# 2_bootleg-4-matrix.net
KiCad netlist of a schematic drawn in Altium Designer
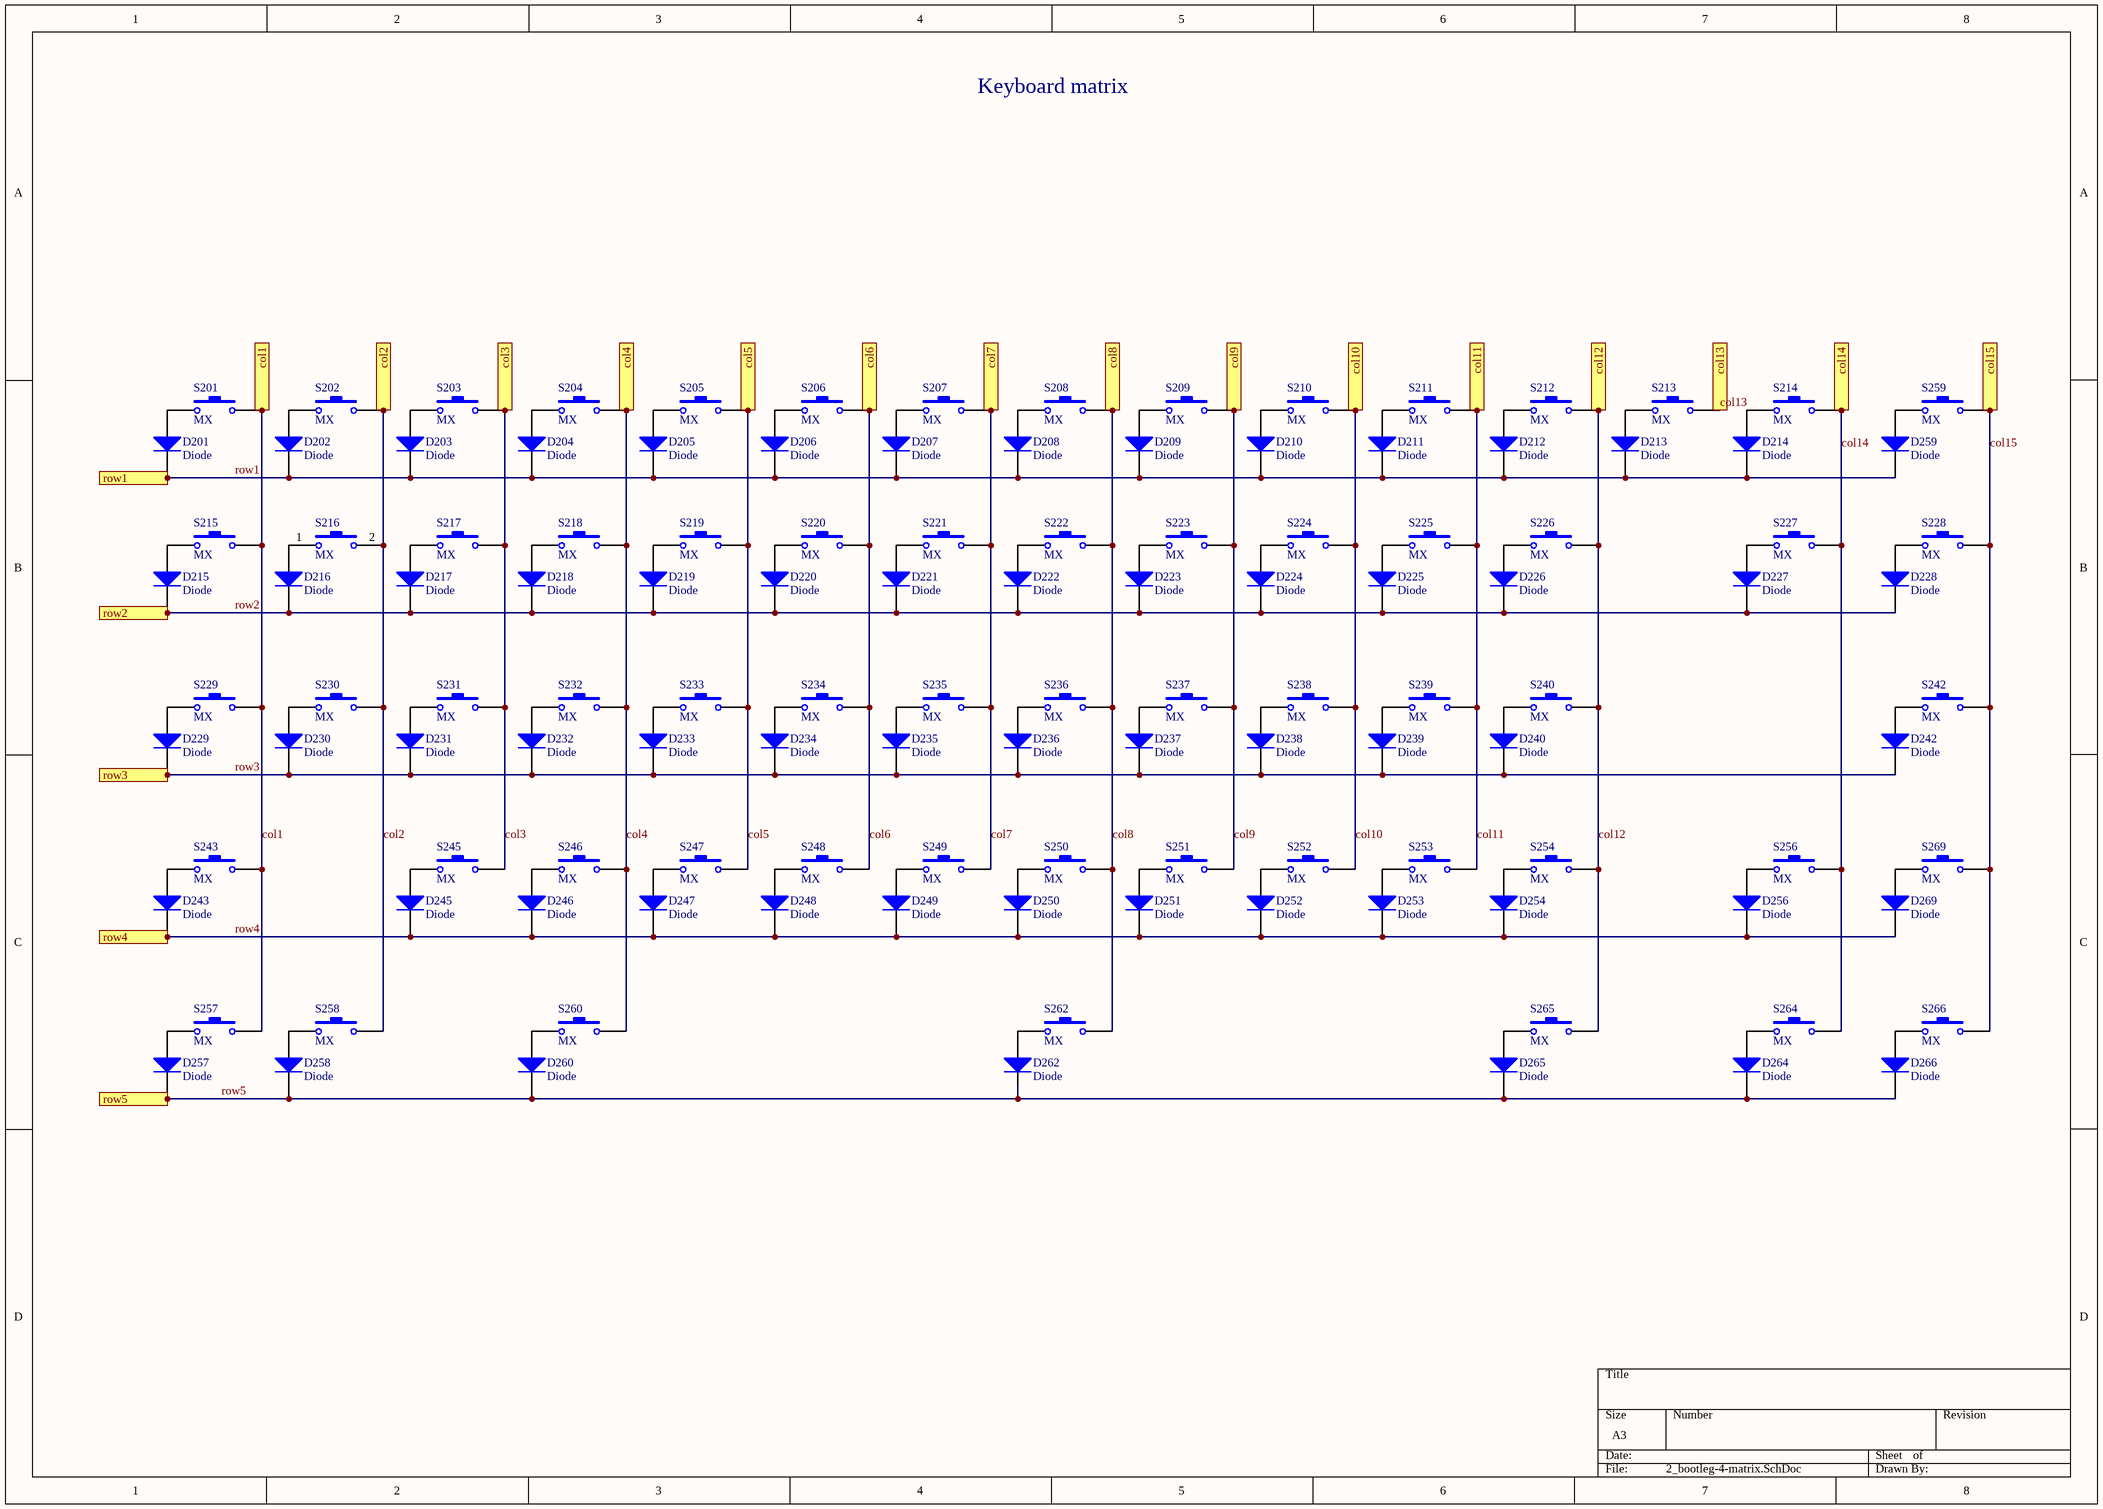
[diagram p0: 2_bootleg-4-matrix.SchDoc]

(export (version "E")
  (design (tool "Eeschema 10.0.6"))
  (components
    (comp (ref "D201")
      (value "Diode")
      (footprint "SOD-123")
      (description "Default Diode")
      (fields (field (name "MFG") "Bourns Inc.") (field (name "LCSC PART #") "C109002"))
      (libsource (lib "Miscellaneous Devices") (part "Diode"))
    )
    (comp (ref "D202")
      (value "Diode")
      (footprint "SOD-123")
      (description "Default Diode")
      (fields (field (name "MFG") "Bourns Inc.") (field (name "LCSC PART #") "C109002"))
      (libsource (lib "Miscellaneous Devices") (part "Diode"))
    )
    (comp (ref "D203")
      (value "Diode")
      (footprint "SOD-123")
      (description "Default Diode")
      (fields (field (name "MFG") "Bourns Inc.") (field (name "LCSC PART #") "C109002"))
      (libsource (lib "Miscellaneous Devices") (part "Diode"))
    )
    (comp (ref "D204")
      (value "Diode")
      (footprint "SOD-123")
      (description "Default Diode")
      (fields (field (name "MFG") "Bourns Inc.") (field (name "LCSC PART #") "C109002"))
      (libsource (lib "Miscellaneous Devices") (part "Diode"))
    )
    (comp (ref "D205")
      (value "Diode")
      (footprint "SOD-123")
      (description "Default Diode")
      (fields (field (name "MFG") "Bourns Inc.") (field (name "LCSC PART #") "C109002"))
      (libsource (lib "Miscellaneous Devices") (part "Diode"))
    )
    (comp (ref "D206")
      (value "Diode")
      (footprint "SOD-123")
      (description "Default Diode")
      (fields (field (name "MFG") "Bourns Inc.") (field (name "LCSC PART #") "C109002"))
      (libsource (lib "Miscellaneous Devices") (part "Diode"))
    )
    (comp (ref "D207")
      (value "Diode")
      (footprint "SOD-123")
      (description "Default Diode")
      (fields (field (name "MFG") "Bourns Inc.") (field (name "LCSC PART #") "C109002"))
      (libsource (lib "Miscellaneous Devices") (part "Diode"))
    )
    (comp (ref "D208")
      (value "Diode")
      (footprint "SOD-123")
      (description "Default Diode")
      (fields (field (name "MFG") "Bourns Inc.") (field (name "LCSC PART #") "C109002"))
      (libsource (lib "Miscellaneous Devices") (part "Diode"))
    )
    (comp (ref "D209")
      (value "Diode")
      (footprint "SOD-123")
      (description "Default Diode")
      (fields (field (name "MFG") "Bourns Inc.") (field (name "LCSC PART #") "C109002"))
      (libsource (lib "Miscellaneous Devices") (part "Diode"))
    )
    (comp (ref "D210")
      (value "Diode")
      (footprint "SOD-123")
      (description "Default Diode")
      (fields (field (name "MFG") "Bourns Inc.") (field (name "LCSC PART #") "C109002"))
      (libsource (lib "Miscellaneous Devices") (part "Diode"))
    )
    (comp (ref "D211")
      (value "Diode")
      (footprint "SOD-123")
      (description "Default Diode")
      (fields (field (name "MFG") "Bourns Inc.") (field (name "LCSC PART #") "C109002"))
      (libsource (lib "Miscellaneous Devices") (part "Diode"))
    )
    (comp (ref "D212")
      (value "Diode")
      (footprint "SOD-123")
      (description "Default Diode")
      (fields (field (name "MFG") "Bourns Inc.") (field (name "LCSC PART #") "C109002"))
      (libsource (lib "Miscellaneous Devices") (part "Diode"))
    )
    (comp (ref "D213")
      (value "Diode")
      (footprint "SOD-123")
      (description "Default Diode")
      (fields (field (name "MFG") "Bourns Inc.") (field (name "LCSC PART #") "C109002"))
      (libsource (lib "Miscellaneous Devices") (part "Diode"))
    )
    (comp (ref "D214")
      (value "Diode")
      (footprint "SOD-123")
      (description "Default Diode")
      (fields (field (name "MFG") "Bourns Inc.") (field (name "LCSC PART #") "C109002"))
      (libsource (lib "Miscellaneous Devices") (part "Diode"))
    )
    (comp (ref "D215")
      (value "Diode")
      (footprint "SOD-123")
      (description "Default Diode")
      (fields (field (name "MFG") "Bourns Inc.") (field (name "LCSC PART #") "C109002"))
      (libsource (lib "Miscellaneous Devices") (part "Diode"))
    )
    (comp (ref "D216")
      (value "Diode")
      (footprint "SOD-123")
      (description "Default Diode")
      (fields (field (name "MFG") "Bourns Inc.") (field (name "LCSC PART #") "C109002"))
      (libsource (lib "Miscellaneous Devices") (part "Diode"))
    )
    (comp (ref "D217")
      (value "Diode")
      (footprint "SOD-123")
      (description "Default Diode")
      (fields (field (name "MFG") "Bourns Inc.") (field (name "LCSC PART #") "C109002"))
      (libsource (lib "Miscellaneous Devices") (part "Diode"))
    )
    (comp (ref "D218")
      (value "Diode")
      (footprint "SOD-123")
      (description "Default Diode")
      (fields (field (name "MFG") "Bourns Inc.") (field (name "LCSC PART #") "C109002"))
      (libsource (lib "Miscellaneous Devices") (part "Diode"))
    )
    (comp (ref "D219")
      (value "Diode")
      (footprint "SOD-123")
      (description "Default Diode")
      (fields (field (name "MFG") "Bourns Inc.") (field (name "LCSC PART #") "C109002"))
      (libsource (lib "Miscellaneous Devices") (part "Diode"))
    )
    (comp (ref "D220")
      (value "Diode")
      (footprint "SOD-123")
      (description "Default Diode")
      (fields (field (name "MFG") "Bourns Inc.") (field (name "LCSC PART #") "C109002"))
      (libsource (lib "Miscellaneous Devices") (part "Diode"))
    )
    (comp (ref "D221")
      (value "Diode")
      (footprint "SOD-123")
      (description "Default Diode")
      (fields (field (name "MFG") "Bourns Inc.") (field (name "LCSC PART #") "C109002"))
      (libsource (lib "Miscellaneous Devices") (part "Diode"))
    )
    (comp (ref "D222")
      (value "Diode")
      (footprint "SOD-123")
      (description "Default Diode")
      (fields (field (name "MFG") "Bourns Inc.") (field (name "LCSC PART #") "C109002"))
      (libsource (lib "Miscellaneous Devices") (part "Diode"))
    )
    (comp (ref "D223")
      (value "Diode")
      (footprint "SOD-123")
      (description "Default Diode")
      (fields (field (name "MFG") "Bourns Inc.") (field (name "LCSC PART #") "C109002"))
      (libsource (lib "Miscellaneous Devices") (part "Diode"))
    )
    (comp (ref "D224")
      (value "Diode")
      (footprint "SOD-123")
      (description "Default Diode")
      (fields (field (name "MFG") "Bourns Inc.") (field (name "LCSC PART #") "C109002"))
      (libsource (lib "Miscellaneous Devices") (part "Diode"))
    )
    (comp (ref "D225")
      (value "Diode")
      (footprint "SOD-123")
      (description "Default Diode")
      (fields (field (name "MFG") "Bourns Inc.") (field (name "LCSC PART #") "C109002"))
      (libsource (lib "Miscellaneous Devices") (part "Diode"))
    )
    (comp (ref "D226")
      (value "Diode")
      (footprint "SOD-123")
      (description "Default Diode")
      (fields (field (name "MFG") "Bourns Inc.") (field (name "LCSC PART #") "C109002"))
      (libsource (lib "Miscellaneous Devices") (part "Diode"))
    )
    (comp (ref "D227")
      (value "Diode")
      (footprint "SOD-123")
      (description "Default Diode")
      (fields (field (name "MFG") "Bourns Inc.") (field (name "LCSC PART #") "C109002"))
      (libsource (lib "Miscellaneous Devices") (part "Diode"))
    )
    (comp (ref "D228")
      (value "Diode")
      (footprint "SOD-123")
      (description "Default Diode")
      (fields (field (name "MFG") "Bourns Inc.") (field (name "LCSC PART #") "C109002"))
      (libsource (lib "Miscellaneous Devices") (part "Diode"))
    )
    (comp (ref "D229")
      (value "Diode")
      (footprint "SOD-123")
      (description "Default Diode")
      (fields (field (name "MFG") "Bourns Inc.") (field (name "LCSC PART #") "C109002"))
      (libsource (lib "Miscellaneous Devices") (part "Diode"))
    )
    (comp (ref "D230")
      (value "Diode")
      (footprint "SOD-123")
      (description "Default Diode")
      (fields (field (name "MFG") "Bourns Inc.") (field (name "LCSC PART #") "C109002"))
      (libsource (lib "Miscellaneous Devices") (part "Diode"))
    )
    (comp (ref "D231")
      (value "Diode")
      (footprint "SOD-123")
      (description "Default Diode")
      (fields (field (name "MFG") "Bourns Inc.") (field (name "LCSC PART #") "C109002"))
      (libsource (lib "Miscellaneous Devices") (part "Diode"))
    )
    (comp (ref "D232")
      (value "Diode")
      (footprint "SOD-123")
      (description "Default Diode")
      (fields (field (name "MFG") "Bourns Inc.") (field (name "LCSC PART #") "C109002"))
      (libsource (lib "Miscellaneous Devices") (part "Diode"))
    )
    (comp (ref "D233")
      (value "Diode")
      (footprint "SOD-123")
      (description "Default Diode")
      (fields (field (name "MFG") "Bourns Inc.") (field (name "LCSC PART #") "C109002"))
      (libsource (lib "Miscellaneous Devices") (part "Diode"))
    )
    (comp (ref "D234")
      (value "Diode")
      (footprint "SOD-123")
      (description "Default Diode")
      (fields (field (name "MFG") "Bourns Inc.") (field (name "LCSC PART #") "C109002"))
      (libsource (lib "Miscellaneous Devices") (part "Diode"))
    )
    (comp (ref "D235")
      (value "Diode")
      (footprint "SOD-123")
      (description "Default Diode")
      (fields (field (name "MFG") "Bourns Inc.") (field (name "LCSC PART #") "C109002"))
      (libsource (lib "Miscellaneous Devices") (part "Diode"))
    )
    (comp (ref "D236")
      (value "Diode")
      (footprint "SOD-123")
      (description "Default Diode")
      (fields (field (name "MFG") "Bourns Inc.") (field (name "LCSC PART #") "C109002"))
      (libsource (lib "Miscellaneous Devices") (part "Diode"))
    )
    (comp (ref "D237")
      (value "Diode")
      (footprint "SOD-123")
      (description "Default Diode")
      (fields (field (name "MFG") "Bourns Inc.") (field (name "LCSC PART #") "C109002"))
      (libsource (lib "Miscellaneous Devices") (part "Diode"))
    )
    (comp (ref "D238")
      (value "Diode")
      (footprint "SOD-123")
      (description "Default Diode")
      (fields (field (name "MFG") "Bourns Inc.") (field (name "LCSC PART #") "C109002"))
      (libsource (lib "Miscellaneous Devices") (part "Diode"))
    )
    (comp (ref "D239")
      (value "Diode")
      (footprint "SOD-123")
      (description "Default Diode")
      (fields (field (name "MFG") "Bourns Inc.") (field (name "LCSC PART #") "C109002"))
      (libsource (lib "Miscellaneous Devices") (part "Diode"))
    )
    (comp (ref "D240")
      (value "Diode")
      (footprint "SOD-123")
      (description "Default Diode")
      (fields (field (name "MFG") "Bourns Inc.") (field (name "LCSC PART #") "C109002"))
      (libsource (lib "Miscellaneous Devices") (part "Diode"))
    )
    (comp (ref "D242")
      (value "Diode")
      (footprint "SOD-123")
      (description "Default Diode")
      (fields (field (name "MFG") "Bourns Inc.") (field (name "LCSC PART #") "C109002"))
      (libsource (lib "Miscellaneous Devices") (part "Diode"))
    )
    (comp (ref "D243")
      (value "Diode")
      (footprint "SOD-123")
      (description "Default Diode")
      (fields (field (name "MFG") "Bourns Inc.") (field (name "LCSC PART #") "C109002"))
      (libsource (lib "Miscellaneous Devices") (part "Diode"))
    )
    (comp (ref "D245")
      (value "Diode")
      (footprint "SOD-123")
      (description "Default Diode")
      (fields (field (name "MFG") "Bourns Inc.") (field (name "LCSC PART #") "C109002"))
      (libsource (lib "Miscellaneous Devices") (part "Diode"))
    )
    (comp (ref "D246")
      (value "Diode")
      (footprint "SOD-123")
      (description "Default Diode")
      (fields (field (name "MFG") "Bourns Inc.") (field (name "LCSC PART #") "C109002"))
      (libsource (lib "Miscellaneous Devices") (part "Diode"))
    )
    (comp (ref "D247")
      (value "Diode")
      (footprint "SOD-123")
      (description "Default Diode")
      (fields (field (name "MFG") "Bourns Inc.") (field (name "LCSC PART #") "C109002"))
      (libsource (lib "Miscellaneous Devices") (part "Diode"))
    )
    (comp (ref "D248")
      (value "Diode")
      (footprint "SOD-123")
      (description "Default Diode")
      (fields (field (name "MFG") "Bourns Inc.") (field (name "LCSC PART #") "C109002"))
      (libsource (lib "Miscellaneous Devices") (part "Diode"))
    )
    (comp (ref "D249")
      (value "Diode")
      (footprint "SOD-123")
      (description "Default Diode")
      (fields (field (name "MFG") "Bourns Inc.") (field (name "LCSC PART #") "C109002"))
      (libsource (lib "Miscellaneous Devices") (part "Diode"))
    )
    (comp (ref "D250")
      (value "Diode")
      (footprint "SOD-123")
      (description "Default Diode")
      (fields (field (name "MFG") "Bourns Inc.") (field (name "LCSC PART #") "C109002"))
      (libsource (lib "Miscellaneous Devices") (part "Diode"))
    )
    (comp (ref "D251")
      (value "Diode")
      (footprint "SOD-123")
      (description "Default Diode")
      (fields (field (name "MFG") "Bourns Inc.") (field (name "LCSC PART #") "C109002"))
      (libsource (lib "Miscellaneous Devices") (part "Diode"))
    )
    (comp (ref "D252")
      (value "Diode")
      (footprint "SOD-123")
      (description "Default Diode")
      (fields (field (name "MFG") "Bourns Inc.") (field (name "LCSC PART #") "C109002"))
      (libsource (lib "Miscellaneous Devices") (part "Diode"))
    )
    (comp (ref "D253")
      (value "Diode")
      (footprint "SOD-123")
      (description "Default Diode")
      (fields (field (name "MFG") "Bourns Inc.") (field (name "LCSC PART #") "C109002"))
      (libsource (lib "Miscellaneous Devices") (part "Diode"))
    )
    (comp (ref "D254")
      (value "Diode")
      (footprint "SOD-123")
      (description "Default Diode")
      (fields (field (name "MFG") "Bourns Inc.") (field (name "LCSC PART #") "C109002"))
      (libsource (lib "Miscellaneous Devices") (part "Diode"))
    )
    (comp (ref "D256")
      (value "Diode")
      (footprint "SOD-123")
      (description "Default Diode")
      (fields (field (name "MFG") "Bourns Inc.") (field (name "LCSC PART #") "C109002"))
      (libsource (lib "Miscellaneous Devices") (part "Diode"))
    )
    (comp (ref "D257")
      (value "Diode")
      (footprint "SOD-123")
      (description "Default Diode")
      (fields (field (name "MFG") "Bourns Inc.") (field (name "LCSC PART #") "C109002"))
      (libsource (lib "Miscellaneous Devices") (part "Diode"))
    )
    (comp (ref "D258")
      (value "Diode")
      (footprint "SOD-123")
      (description "Default Diode")
      (fields (field (name "MFG") "Bourns Inc.") (field (name "LCSC PART #") "C109002"))
      (libsource (lib "Miscellaneous Devices") (part "Diode"))
    )
    (comp (ref "D259")
      (value "Diode")
      (footprint "SOD-123")
      (description "Default Diode")
      (fields (field (name "MFG") "Bourns Inc.") (field (name "LCSC PART #") "C109002"))
      (libsource (lib "Miscellaneous Devices") (part "Diode"))
    )
    (comp (ref "D260")
      (value "Diode")
      (footprint "SOD-123")
      (description "Default Diode")
      (fields (field (name "MFG") "Bourns Inc.") (field (name "LCSC PART #") "C109002"))
      (libsource (lib "Miscellaneous Devices") (part "Diode"))
    )
    (comp (ref "D262")
      (value "Diode")
      (footprint "SOD-123")
      (description "Default Diode")
      (fields (field (name "MFG") "Bourns Inc.") (field (name "LCSC PART #") "C109002"))
      (libsource (lib "Miscellaneous Devices") (part "Diode"))
    )
    (comp (ref "D264")
      (value "Diode")
      (footprint "SOD-123")
      (description "Default Diode")
      (fields (field (name "MFG") "Bourns Inc.") (field (name "LCSC PART #") "C109002"))
      (libsource (lib "Miscellaneous Devices") (part "Diode"))
    )
    (comp (ref "D265")
      (value "Diode")
      (footprint "SOD-123")
      (description "Default Diode")
      (fields (field (name "MFG") "Bourns Inc.") (field (name "LCSC PART #") "C109002"))
      (libsource (lib "Miscellaneous Devices") (part "Diode"))
    )
    (comp (ref "D266")
      (value "Diode")
      (footprint "SOD-123")
      (description "Default Diode")
      (fields (field (name "MFG") "Bourns Inc.") (field (name "LCSC PART #") "C109002"))
      (libsource (lib "Miscellaneous Devices") (part "Diode"))
    )
    (comp (ref "D269")
      (value "Diode")
      (footprint "SOD-123")
      (description "Default Diode")
      (fields (field (name "MFG") "Bourns Inc.") (field (name "LCSC PART #") "C109002"))
      (libsource (lib "Miscellaneous Devices") (part "Diode"))
    )
    (comp (ref "S201")
      (value "MX")
      (footprint "MX-switch - switched pol")
      (description "Switch")
      (libsource (lib "Miscellaneous Devices") (part "SW-PB"))
    )
    (comp (ref "S202")
      (value "MX")
      (footprint "MX-switch - switched pol")
      (description "Switch")
      (libsource (lib "Miscellaneous Devices") (part "SW-PB"))
    )
    (comp (ref "S203")
      (value "MX")
      (footprint "MX-switch - switched pol")
      (description "Switch")
      (libsource (lib "Miscellaneous Devices") (part "SW-PB"))
    )
    (comp (ref "S204")
      (value "MX")
      (footprint "MX-switch - switched pol")
      (description "Switch")
      (libsource (lib "Miscellaneous Devices") (part "SW-PB"))
    )
    (comp (ref "S205")
      (value "MX")
      (footprint "MX-switch - switched pol")
      (description "Switch")
      (libsource (lib "Miscellaneous Devices") (part "SW-PB"))
    )
    (comp (ref "S206")
      (value "MX")
      (footprint "MX-switch - switched pol")
      (description "Switch")
      (libsource (lib "Miscellaneous Devices") (part "SW-PB"))
    )
    (comp (ref "S207")
      (value "MX")
      (footprint "MX-switch - switched pol")
      (description "Switch")
      (libsource (lib "Miscellaneous Devices") (part "SW-PB"))
    )
    (comp (ref "S208")
      (value "MX")
      (footprint "MX-switch - switched pol")
      (description "Switch")
      (libsource (lib "Miscellaneous Devices") (part "SW-PB"))
    )
    (comp (ref "S209")
      (value "MX")
      (footprint "MX-switch - switched pol")
      (description "Switch")
      (libsource (lib "Miscellaneous Devices") (part "SW-PB"))
    )
    (comp (ref "S210")
      (value "MX")
      (footprint "MX-switch - switched pol")
      (description "Switch")
      (libsource (lib "Miscellaneous Devices") (part "SW-PB"))
    )
    (comp (ref "S211")
      (value "MX")
      (footprint "MX-switch - switched pol")
      (description "Switch")
      (libsource (lib "Miscellaneous Devices") (part "SW-PB"))
    )
    (comp (ref "S212")
      (value "MX")
      (footprint "MX-switch - switched pol")
      (description "Switch")
      (libsource (lib "Miscellaneous Devices") (part "SW-PB"))
    )
    (comp (ref "S213")
      (value "MX")
      (footprint "MX-switch - switched pol")
      (description "Switch")
      (libsource (lib "Miscellaneous Devices") (part "SW-PB"))
    )
    (comp (ref "S214")
      (value "MX")
      (footprint "MX-switch - switched pol")
      (description "Switch")
      (libsource (lib "Miscellaneous Devices") (part "SW-PB"))
    )
    (comp (ref "S215")
      (value "MX")
      (footprint "MX-switch - 1.5U")
      (description "TAB")
      (libsource (lib "Miscellaneous Devices") (part "SW-PB"))
    )
    (comp (ref "S216")
      (value "MX")
      (footprint "MX-switch - switched pol")
      (description "Switch")
      (libsource (lib "") (part "SW-PB_1"))
    )
    (comp (ref "S217")
      (value "MX")
      (footprint "MX-switch - switched pol")
      (description "Switch")
      (libsource (lib "Miscellaneous Devices") (part "SW-PB"))
    )
    (comp (ref "S218")
      (value "MX")
      (footprint "MX-switch - switched pol")
      (description "Switch")
      (libsource (lib "Miscellaneous Devices") (part "SW-PB"))
    )
    (comp (ref "S219")
      (value "MX")
      (footprint "MX-switch - switched pol")
      (description "Switch")
      (libsource (lib "Miscellaneous Devices") (part "SW-PB"))
    )
    (comp (ref "S220")
      (value "MX")
      (footprint "MX-switch - switched pol")
      (description "Switch")
      (libsource (lib "Miscellaneous Devices") (part "SW-PB"))
    )
    (comp (ref "S221")
      (value "MX")
      (footprint "MX-switch - switched pol")
      (description "Switch")
      (libsource (lib "Miscellaneous Devices") (part "SW-PB"))
    )
    (comp (ref "S222")
      (value "MX")
      (footprint "MX-switch - switched pol")
      (description "Switch")
      (libsource (lib "Miscellaneous Devices") (part "SW-PB"))
    )
    (comp (ref "S223")
      (value "MX")
      (footprint "MX-switch - switched pol")
      (description "Switch")
      (libsource (lib "Miscellaneous Devices") (part "SW-PB"))
    )
    (comp (ref "S224")
      (value "MX")
      (footprint "MX-switch - switched pol")
      (description "Switch")
      (libsource (lib "Miscellaneous Devices") (part "SW-PB"))
    )
    (comp (ref "S225")
      (value "MX")
      (footprint "MX-switch - switched pol")
      (description "Switch")
      (libsource (lib "Miscellaneous Devices") (part "SW-PB"))
    )
    (comp (ref "S226")
      (value "MX")
      (footprint "MX-switch")
      (description "Switch")
      (libsource (lib "Miscellaneous Devices") (part "SW-PB"))
    )
    (comp (ref "S227")
      (value "MX")
      (footprint "MX-switch - switched pol")
      (description "Switch")
      (libsource (lib "Miscellaneous Devices") (part "SW-PB"))
    )
    (comp (ref "S228")
      (value "MX")
      (footprint "MX-switch - 1.5U")
      (description "Switch")
      (libsource (lib "Miscellaneous Devices") (part "SW-PB"))
    )
    (comp (ref "S229")
      (value "MX")
      (footprint "MX-switch - CAPS")
      (description "Switch")
      (libsource (lib "Miscellaneous Devices") (part "SW-PB"))
    )
    (comp (ref "S230")
      (value "MX")
      (footprint "MX-switch - switched pol")
      (description "Switch")
      (libsource (lib "Miscellaneous Devices") (part "SW-PB"))
    )
    (comp (ref "S231")
      (value "MX")
      (footprint "MX-switch - switched pol")
      (description "Switch")
      (libsource (lib "Miscellaneous Devices") (part "SW-PB"))
    )
    (comp (ref "S232")
      (value "MX")
      (footprint "MX-switch - switched pol")
      (description "Switch")
      (libsource (lib "Miscellaneous Devices") (part "SW-PB"))
    )
    (comp (ref "S233")
      (value "MX")
      (footprint "MX-switch - switched pol")
      (description "Switch")
      (libsource (lib "Miscellaneous Devices") (part "SW-PB"))
    )
    (comp (ref "S234")
      (value "MX")
      (footprint "MX-switch - switched pol")
      (description "Switch")
      (libsource (lib "Miscellaneous Devices") (part "SW-PB"))
    )
    (comp (ref "S235")
      (value "MX")
      (footprint "MX-switch - switched pol")
      (description "Switch")
      (libsource (lib "Miscellaneous Devices") (part "SW-PB"))
    )
    (comp (ref "S236")
      (value "MX")
      (footprint "MX-switch - switched pol")
      (description "Switch")
      (libsource (lib "Miscellaneous Devices") (part "SW-PB"))
    )
    (comp (ref "S237")
      (value "MX")
      (footprint "MX-switch - switched pol")
      (description "Switch")
      (libsource (lib "Miscellaneous Devices") (part "SW-PB"))
    )
    (comp (ref "S238")
      (value "MX")
      (footprint "MX-switch - switched pol")
      (description "Switch")
      (libsource (lib "Miscellaneous Devices") (part "SW-PB"))
    )
    (comp (ref "S239")
      (value "MX")
      (footprint "MX-switch")
      (description "Switch")
      (libsource (lib "Miscellaneous Devices") (part "SW-PB"))
    )
    (comp (ref "S240")
      (value "MX")
      (footprint "MX-switch - switched pol")
      (description "Switch")
      (libsource (lib "Miscellaneous Devices") (part "SW-PB"))
    )
    (comp (ref "S242")
      (value "MX")
      (footprint "MX-switch - Enter_ANSI")
      (description "Switch")
      (libsource (lib "Miscellaneous Devices") (part "SW-PB"))
    )
    (comp (ref "S243")
      (value "MX")
      (footprint "MX-switch - 2.25U")
      (description "Switch")
      (libsource (lib "Miscellaneous Devices") (part "SW-PB"))
    )
    (comp (ref "S245")
      (value "MX")
      (footprint "MX-switch - switched pol")
      (description "Switch")
      (libsource (lib "Miscellaneous Devices") (part "SW-PB"))
    )
    (comp (ref "S246")
      (value "MX")
      (footprint "MX-switch - switched pol")
      (description "Switch")
      (libsource (lib "Miscellaneous Devices") (part "SW-PB"))
    )
    (comp (ref "S247")
      (value "MX")
      (footprint "MX-switch - switched pol")
      (description "Switch")
      (libsource (lib "Miscellaneous Devices") (part "SW-PB"))
    )
    (comp (ref "S248")
      (value "MX")
      (footprint "MX-switch - switched pol")
      (description "Switch")
      (libsource (lib "Miscellaneous Devices") (part "SW-PB"))
    )
    (comp (ref "S249")
      (value "MX")
      (footprint "MX-switch - switched pol")
      (description "Switch")
      (libsource (lib "Miscellaneous Devices") (part "SW-PB"))
    )
    (comp (ref "S250")
      (value "MX")
      (footprint "MX-switch - switched pol")
      (description "Switch")
      (libsource (lib "Miscellaneous Devices") (part "SW-PB"))
    )
    (comp (ref "S251")
      (value "MX")
      (footprint "MX-switch - switched pol")
      (description "Switch")
      (libsource (lib "Miscellaneous Devices") (part "SW-PB"))
    )
    (comp (ref "S252")
      (value "MX")
      (footprint "MX-switch - switched pol")
      (description "Switch")
      (libsource (lib "Miscellaneous Devices") (part "SW-PB"))
    )
    (comp (ref "S253")
      (value "MX")
      (footprint "MX-switch - switched pol")
      (description "Switch")
      (libsource (lib "Miscellaneous Devices") (part "SW-PB"))
    )
    (comp (ref "S254")
      (value "MX")
      (footprint "MX-switch - switched pol")
      (description "Switch")
      (libsource (lib "Miscellaneous Devices") (part "SW-PB"))
    )
    (comp (ref "S256")
      (value "MX")
      (footprint "MX-switch - right shift")
      (description "Switch")
      (libsource (lib "Miscellaneous Devices") (part "SW-PB"))
    )
    (comp (ref "S257")
      (value "MX")
      (footprint "MX-switch - 1.5U - switched pol")
      (description "Switch")
      (libsource (lib "Miscellaneous Devices") (part "SW-PB"))
    )
    (comp (ref "S258")
      (value "MX")
      (footprint "MX-switch")
      (description "Switch")
      (libsource (lib "Miscellaneous Devices") (part "SW-PB"))
    )
    (comp (ref "S259")
      (value "MX")
      (footprint "MX-switch - backspace")
      (description "Switch")
      (libsource (lib "Miscellaneous Devices") (part "SW-PB"))
    )
    (comp (ref "S260")
      (value "MX")
      (footprint "MX-switch - 1.5U")
      (description "Switch")
      (libsource (lib "Miscellaneous Devices") (part "SW-PB"))
    )
    (comp (ref "S262")
      (value "MX")
      (footprint "MX-switch - 7u space")
      (description "Switch")
      (libsource (lib "Miscellaneous Devices") (part "SW-PB"))
    )
    (comp (ref "S264")
      (value "MX")
      (footprint "MX-switch")
      (description "Switch")
      (libsource (lib "Miscellaneous Devices") (part "SW-PB"))
    )
    (comp (ref "S265")
      (value "MX")
      (footprint "MX-switch - 1.5U - switched pol")
      (description "Switch")
      (libsource (lib "Miscellaneous Devices") (part "SW-PB"))
    )
    (comp (ref "S266")
      (value "MX")
      (footprint "MX-switch - 1.5U")
      (description "Switch")
      (libsource (lib "Miscellaneous Devices") (part "SW-PB"))
    )
    (comp (ref "S269")
      (value "MX")
      (footprint "MX-switch")
      (description "Switch")
      (libsource (lib "Miscellaneous Devices") (part "SW-PB"))
    )
  )
  (nets
    (net (code "1") (name "/col1") (class "Default")
      (node (ref "S201") (pin "2") (pinfunction "2_2") (pintype "passive"))
      (node (ref "S215") (pin "2") (pinfunction "2_2") (pintype "passive"))
      (node (ref "S229") (pin "2") (pinfunction "2_2") (pintype "passive"))
      (node (ref "S243") (pin "1") (pinfunction "1_1") (pintype "passive"))
      (node (ref "S257") (pin "2") (pinfunction "2_2") (pintype "passive"))
    )
    (net (code "2") (name "/col2") (class "Default")
      (node (ref "S202") (pin "2") (pinfunction "2_2") (pintype "passive"))
      (node (ref "S216") (pin "2") (pinfunction "2_2") (pintype "passive"))
      (node (ref "S230") (pin "2") (pinfunction "2_2") (pintype "passive"))
      (node (ref "S258") (pin "2") (pinfunction "2_2") (pintype "passive"))
    )
    (net (code "3") (name "/col3") (class "Default")
      (node (ref "S203") (pin "2") (pinfunction "2_2") (pintype "passive"))
      (node (ref "S217") (pin "2") (pinfunction "2_2") (pintype "passive"))
      (node (ref "S231") (pin "2") (pinfunction "2_2") (pintype "passive"))
      (node (ref "S245") (pin "2") (pinfunction "2_2") (pintype "passive"))
    )
    (net (code "4") (name "/col4") (class "Default")
      (node (ref "S204") (pin "2") (pinfunction "2_2") (pintype "passive"))
      (node (ref "S218") (pin "2") (pinfunction "2_2") (pintype "passive"))
      (node (ref "S232") (pin "2") (pinfunction "2_2") (pintype "passive"))
      (node (ref "S246") (pin "2") (pinfunction "2_2") (pintype "passive"))
      (node (ref "S260") (pin "2") (pinfunction "2_2") (pintype "passive"))
    )
    (net (code "5") (name "/col5") (class "Default")
      (node (ref "S205") (pin "2") (pinfunction "2_2") (pintype "passive"))
      (node (ref "S219") (pin "2") (pinfunction "2_2") (pintype "passive"))
      (node (ref "S233") (pin "2") (pinfunction "2_2") (pintype "passive"))
      (node (ref "S247") (pin "2") (pinfunction "2_2") (pintype "passive"))
    )
    (net (code "6") (name "/col6") (class "Default")
      (node (ref "S206") (pin "2") (pinfunction "2_2") (pintype "passive"))
      (node (ref "S220") (pin "2") (pinfunction "2_2") (pintype "passive"))
      (node (ref "S234") (pin "2") (pinfunction "2_2") (pintype "passive"))
      (node (ref "S248") (pin "2") (pinfunction "2_2") (pintype "passive"))
    )
    (net (code "7") (name "/col7") (class "Default")
      (node (ref "S207") (pin "2") (pinfunction "2_2") (pintype "passive"))
      (node (ref "S221") (pin "2") (pinfunction "2_2") (pintype "passive"))
      (node (ref "S235") (pin "2") (pinfunction "2_2") (pintype "passive"))
      (node (ref "S249") (pin "2") (pinfunction "2_2") (pintype "passive"))
    )
    (net (code "8") (name "/col8") (class "Default")
      (node (ref "S208") (pin "2") (pinfunction "2_2") (pintype "passive"))
      (node (ref "S222") (pin "2") (pinfunction "2_2") (pintype "passive"))
      (node (ref "S236") (pin "2") (pinfunction "2_2") (pintype "passive"))
      (node (ref "S250") (pin "2") (pinfunction "2_2") (pintype "passive"))
      (node (ref "S262") (pin "2") (pinfunction "2_2") (pintype "passive"))
    )
    (net (code "9") (name "/col9") (class "Default")
      (node (ref "S209") (pin "2") (pinfunction "2_2") (pintype "passive"))
      (node (ref "S223") (pin "2") (pinfunction "2_2") (pintype "passive"))
      (node (ref "S237") (pin "2") (pinfunction "2_2") (pintype "passive"))
      (node (ref "S251") (pin "2") (pinfunction "2_2") (pintype "passive"))
    )
    (net (code "10") (name "/col10") (class "Default")
      (node (ref "S210") (pin "2") (pinfunction "2_2") (pintype "passive"))
      (node (ref "S224") (pin "2") (pinfunction "2_2") (pintype "passive"))
      (node (ref "S238") (pin "2") (pinfunction "2_2") (pintype "passive"))
      (node (ref "S252") (pin "2") (pinfunction "2_2") (pintype "passive"))
    )
    (net (code "11") (name "/col11") (class "Default")
      (node (ref "S211") (pin "2") (pinfunction "2_2") (pintype "passive"))
      (node (ref "S225") (pin "2") (pinfunction "2_2") (pintype "passive"))
      (node (ref "S239") (pin "2") (pinfunction "2_2") (pintype "passive"))
      (node (ref "S253") (pin "2") (pinfunction "2_2") (pintype "passive"))
    )
    (net (code "12") (name "/col12") (class "Default")
      (node (ref "S212") (pin "2") (pinfunction "2_2") (pintype "passive"))
      (node (ref "S226") (pin "2") (pinfunction "2_2") (pintype "passive"))
      (node (ref "S240") (pin "2") (pinfunction "2_2") (pintype "passive"))
      (node (ref "S254") (pin "2") (pinfunction "2_2") (pintype "passive"))
      (node (ref "S265") (pin "2") (pinfunction "2_2") (pintype "passive"))
    )
    (net (code "13") (name "/col13") (class "Default")
      (node (ref "S213") (pin "2") (pinfunction "2_2") (pintype "passive"))
    )
    (net (code "14") (name "/col14") (class "Default")
      (node (ref "S214") (pin "2") (pinfunction "2_2") (pintype "passive"))
      (node (ref "S227") (pin "2") (pinfunction "2_2") (pintype "passive"))
      (node (ref "S256") (pin "2") (pinfunction "2_2") (pintype "passive"))
      (node (ref "S264") (pin "2") (pinfunction "2_2") (pintype "passive"))
    )
    (net (code "15") (name "/col15") (class "Default")
      (node (ref "S228") (pin "2") (pinfunction "2_2") (pintype "passive"))
      (node (ref "S242") (pin "1") (pinfunction "1_1") (pintype "passive"))
      (node (ref "S259") (pin "2") (pinfunction "2_2") (pintype "passive"))
      (node (ref "S266") (pin "2") (pinfunction "2_2") (pintype "passive"))
      (node (ref "S269") (pin "2") (pinfunction "2_2") (pintype "passive"))
    )
    (net (code "16") (name "/row1") (class "Default")
      (node (ref "D201") (pin "2") (pinfunction "K_2") (pintype "passive"))
      (node (ref "D202") (pin "2") (pinfunction "K_2") (pintype "passive"))
      (node (ref "D203") (pin "2") (pinfunction "K_2") (pintype "passive"))
      (node (ref "D204") (pin "2") (pinfunction "K_2") (pintype "passive"))
      (node (ref "D205") (pin "2") (pinfunction "K_2") (pintype "passive"))
      (node (ref "D206") (pin "2") (pinfunction "K_2") (pintype "passive"))
      (node (ref "D207") (pin "2") (pinfunction "K_2") (pintype "passive"))
      (node (ref "D208") (pin "2") (pinfunction "K_2") (pintype "passive"))
      (node (ref "D209") (pin "2") (pinfunction "K_2") (pintype "passive"))
      (node (ref "D210") (pin "2") (pinfunction "K_2") (pintype "passive"))
      (node (ref "D211") (pin "2") (pinfunction "K_2") (pintype "passive"))
      (node (ref "D212") (pin "2") (pinfunction "K_2") (pintype "passive"))
      (node (ref "D213") (pin "2") (pinfunction "K_2") (pintype "passive"))
      (node (ref "D214") (pin "2") (pinfunction "K_2") (pintype "passive"))
      (node (ref "D259") (pin "2") (pinfunction "K_2") (pintype "passive"))
    )
    (net (code "17") (name "/row2") (class "Default")
      (node (ref "D215") (pin "2") (pinfunction "K_2") (pintype "passive"))
      (node (ref "D216") (pin "2") (pinfunction "K_2") (pintype "passive"))
      (node (ref "D217") (pin "2") (pinfunction "K_2") (pintype "passive"))
      (node (ref "D218") (pin "2") (pinfunction "K_2") (pintype "passive"))
      (node (ref "D219") (pin "2") (pinfunction "K_2") (pintype "passive"))
      (node (ref "D220") (pin "2") (pinfunction "K_2") (pintype "passive"))
      (node (ref "D221") (pin "2") (pinfunction "K_2") (pintype "passive"))
      (node (ref "D222") (pin "2") (pinfunction "K_2") (pintype "passive"))
      (node (ref "D223") (pin "2") (pinfunction "K_2") (pintype "passive"))
      (node (ref "D224") (pin "2") (pinfunction "K_2") (pintype "passive"))
      (node (ref "D225") (pin "2") (pinfunction "K_2") (pintype "passive"))
      (node (ref "D226") (pin "2") (pinfunction "K_2") (pintype "passive"))
      (node (ref "D227") (pin "2") (pinfunction "K_2") (pintype "passive"))
      (node (ref "D228") (pin "2") (pinfunction "K_2") (pintype "passive"))
    )
    (net (code "18") (name "/row3") (class "Default")
      (node (ref "D229") (pin "2") (pinfunction "K_2") (pintype "passive"))
      (node (ref "D230") (pin "2") (pinfunction "K_2") (pintype "passive"))
      (node (ref "D231") (pin "2") (pinfunction "K_2") (pintype "passive"))
      (node (ref "D232") (pin "2") (pinfunction "K_2") (pintype "passive"))
      (node (ref "D233") (pin "2") (pinfunction "K_2") (pintype "passive"))
      (node (ref "D234") (pin "2") (pinfunction "K_2") (pintype "passive"))
      (node (ref "D235") (pin "2") (pinfunction "K_2") (pintype "passive"))
      (node (ref "D236") (pin "2") (pinfunction "K_2") (pintype "passive"))
      (node (ref "D237") (pin "2") (pinfunction "K_2") (pintype "passive"))
      (node (ref "D238") (pin "2") (pinfunction "K_2") (pintype "passive"))
      (node (ref "D239") (pin "2") (pinfunction "K_2") (pintype "passive"))
      (node (ref "D240") (pin "2") (pinfunction "K_2") (pintype "passive"))
      (node (ref "D242") (pin "2") (pinfunction "K_2") (pintype "passive"))
    )
    (net (code "19") (name "/row4") (class "Default")
      (node (ref "D243") (pin "2") (pinfunction "K_2") (pintype "passive"))
      (node (ref "D245") (pin "2") (pinfunction "K_2") (pintype "passive"))
      (node (ref "D246") (pin "2") (pinfunction "K_2") (pintype "passive"))
      (node (ref "D247") (pin "2") (pinfunction "K_2") (pintype "passive"))
      (node (ref "D248") (pin "2") (pinfunction "K_2") (pintype "passive"))
      (node (ref "D249") (pin "2") (pinfunction "K_2") (pintype "passive"))
      (node (ref "D250") (pin "2") (pinfunction "K_2") (pintype "passive"))
      (node (ref "D251") (pin "2") (pinfunction "K_2") (pintype "passive"))
      (node (ref "D252") (pin "2") (pinfunction "K_2") (pintype "passive"))
      (node (ref "D253") (pin "2") (pinfunction "K_2") (pintype "passive"))
      (node (ref "D254") (pin "2") (pinfunction "K_2") (pintype "passive"))
      (node (ref "D256") (pin "2") (pinfunction "K_2") (pintype "passive"))
      (node (ref "D269") (pin "2") (pinfunction "K_2") (pintype "passive"))
    )
    (net (code "20") (name "/row5") (class "Default")
      (node (ref "D257") (pin "2") (pinfunction "K_2") (pintype "passive"))
      (node (ref "D258") (pin "2") (pinfunction "K_2") (pintype "passive"))
      (node (ref "D260") (pin "2") (pinfunction "K_2") (pintype "passive"))
      (node (ref "D262") (pin "2") (pinfunction "K_2") (pintype "passive"))
      (node (ref "D264") (pin "2") (pinfunction "K_2") (pintype "passive"))
      (node (ref "D265") (pin "2") (pinfunction "K_2") (pintype "passive"))
      (node (ref "D266") (pin "2") (pinfunction "K_2") (pintype "passive"))
    )
    (net (code "21") (name "Net-(D201-A)") (class "Default")
      (node (ref "D201") (pin "1") (pinfunction "A_1") (pintype "passive"))
      (node (ref "S201") (pin "1") (pinfunction "1_1") (pintype "passive"))
    )
    (net (code "22") (name "Net-(D202-A)") (class "Default")
      (node (ref "D202") (pin "1") (pinfunction "A_1") (pintype "passive"))
      (node (ref "S202") (pin "1") (pinfunction "1_1") (pintype "passive"))
    )
    (net (code "23") (name "Net-(D203-A)") (class "Default")
      (node (ref "D203") (pin "1") (pinfunction "A_1") (pintype "passive"))
      (node (ref "S203") (pin "1") (pinfunction "1_1") (pintype "passive"))
    )
    (net (code "24") (name "Net-(D204-A)") (class "Default")
      (node (ref "D204") (pin "1") (pinfunction "A_1") (pintype "passive"))
      (node (ref "S204") (pin "1") (pinfunction "1_1") (pintype "passive"))
    )
    (net (code "25") (name "Net-(D205-A)") (class "Default")
      (node (ref "D205") (pin "1") (pinfunction "A_1") (pintype "passive"))
      (node (ref "S205") (pin "1") (pinfunction "1_1") (pintype "passive"))
    )
    (net (code "26") (name "Net-(D206-A)") (class "Default")
      (node (ref "D206") (pin "1") (pinfunction "A_1") (pintype "passive"))
      (node (ref "S206") (pin "1") (pinfunction "1_1") (pintype "passive"))
    )
    (net (code "27") (name "Net-(D207-A)") (class "Default")
      (node (ref "D207") (pin "1") (pinfunction "A_1") (pintype "passive"))
      (node (ref "S207") (pin "1") (pinfunction "1_1") (pintype "passive"))
    )
    (net (code "28") (name "Net-(D208-A)") (class "Default")
      (node (ref "D208") (pin "1") (pinfunction "A_1") (pintype "passive"))
      (node (ref "S208") (pin "1") (pinfunction "1_1") (pintype "passive"))
    )
    (net (code "29") (name "Net-(D209-A)") (class "Default")
      (node (ref "D209") (pin "1") (pinfunction "A_1") (pintype "passive"))
      (node (ref "S209") (pin "1") (pinfunction "1_1") (pintype "passive"))
    )
    (net (code "30") (name "Net-(D210-A)") (class "Default")
      (node (ref "D210") (pin "1") (pinfunction "A_1") (pintype "passive"))
      (node (ref "S210") (pin "1") (pinfunction "1_1") (pintype "passive"))
    )
    (net (code "31") (name "Net-(D211-A)") (class "Default")
      (node (ref "D211") (pin "1") (pinfunction "A_1") (pintype "passive"))
      (node (ref "S211") (pin "1") (pinfunction "1_1") (pintype "passive"))
    )
    (net (code "32") (name "Net-(D212-A)") (class "Default")
      (node (ref "D212") (pin "1") (pinfunction "A_1") (pintype "passive"))
      (node (ref "S212") (pin "1") (pinfunction "1_1") (pintype "passive"))
    )
    (net (code "33") (name "Net-(D213-A)") (class "Default")
      (node (ref "D213") (pin "1") (pinfunction "A_1") (pintype "passive"))
      (node (ref "S213") (pin "1") (pinfunction "1_1") (pintype "passive"))
    )
    (net (code "34") (name "Net-(D214-A)") (class "Default")
      (node (ref "D214") (pin "1") (pinfunction "A_1") (pintype "passive"))
      (node (ref "S214") (pin "1") (pinfunction "1_1") (pintype "passive"))
    )
    (net (code "35") (name "Net-(D215-A)") (class "Default")
      (node (ref "D215") (pin "1") (pinfunction "A_1") (pintype "passive"))
      (node (ref "S215") (pin "1") (pinfunction "1_1") (pintype "passive"))
    )
    (net (code "36") (name "Net-(D216-A)") (class "Default")
      (node (ref "D216") (pin "1") (pinfunction "A_1") (pintype "passive"))
      (node (ref "S216") (pin "1") (pinfunction "1_1") (pintype "passive"))
    )
    (net (code "37") (name "Net-(D217-A)") (class "Default")
      (node (ref "D217") (pin "1") (pinfunction "A_1") (pintype "passive"))
      (node (ref "S217") (pin "1") (pinfunction "1_1") (pintype "passive"))
    )
    (net (code "38") (name "Net-(D218-A)") (class "Default")
      (node (ref "D218") (pin "1") (pinfunction "A_1") (pintype "passive"))
      (node (ref "S218") (pin "1") (pinfunction "1_1") (pintype "passive"))
    )
    (net (code "39") (name "Net-(D219-A)") (class "Default")
      (node (ref "D219") (pin "1") (pinfunction "A_1") (pintype "passive"))
      (node (ref "S219") (pin "1") (pinfunction "1_1") (pintype "passive"))
    )
    (net (code "40") (name "Net-(D220-A)") (class "Default")
      (node (ref "D220") (pin "1") (pinfunction "A_1") (pintype "passive"))
      (node (ref "S220") (pin "1") (pinfunction "1_1") (pintype "passive"))
    )
    (net (code "41") (name "Net-(D221-A)") (class "Default")
      (node (ref "D221") (pin "1") (pinfunction "A_1") (pintype "passive"))
      (node (ref "S221") (pin "1") (pinfunction "1_1") (pintype "passive"))
    )
    (net (code "42") (name "Net-(D222-A)") (class "Default")
      (node (ref "D222") (pin "1") (pinfunction "A_1") (pintype "passive"))
      (node (ref "S222") (pin "1") (pinfunction "1_1") (pintype "passive"))
    )
    (net (code "43") (name "Net-(D223-A)") (class "Default")
      (node (ref "D223") (pin "1") (pinfunction "A_1") (pintype "passive"))
      (node (ref "S223") (pin "1") (pinfunction "1_1") (pintype "passive"))
    )
    (net (code "44") (name "Net-(D224-A)") (class "Default")
      (node (ref "D224") (pin "1") (pinfunction "A_1") (pintype "passive"))
      (node (ref "S224") (pin "1") (pinfunction "1_1") (pintype "passive"))
    )
    (net (code "45") (name "Net-(D225-A)") (class "Default")
      (node (ref "D225") (pin "1") (pinfunction "A_1") (pintype "passive"))
      (node (ref "S225") (pin "1") (pinfunction "1_1") (pintype "passive"))
    )
    (net (code "46") (name "Net-(D226-A)") (class "Default")
      (node (ref "D226") (pin "1") (pinfunction "A_1") (pintype "passive"))
      (node (ref "S226") (pin "1") (pinfunction "1_1") (pintype "passive"))
    )
    (net (code "47") (name "Net-(D227-A)") (class "Default")
      (node (ref "D227") (pin "1") (pinfunction "A_1") (pintype "passive"))
      (node (ref "S227") (pin "1") (pinfunction "1_1") (pintype "passive"))
    )
    (net (code "48") (name "Net-(D228-A)") (class "Default")
      (node (ref "D228") (pin "1") (pinfunction "A_1") (pintype "passive"))
      (node (ref "S228") (pin "1") (pinfunction "1_1") (pintype "passive"))
    )
    (net (code "49") (name "Net-(D229-A)") (class "Default")
      (node (ref "D229") (pin "1") (pinfunction "A_1") (pintype "passive"))
      (node (ref "S229") (pin "1") (pinfunction "1_1") (pintype "passive"))
    )
    (net (code "50") (name "Net-(D230-A)") (class "Default")
      (node (ref "D230") (pin "1") (pinfunction "A_1") (pintype "passive"))
      (node (ref "S230") (pin "1") (pinfunction "1_1") (pintype "passive"))
    )
    (net (code "51") (name "Net-(D231-A)") (class "Default")
      (node (ref "D231") (pin "1") (pinfunction "A_1") (pintype "passive"))
      (node (ref "S231") (pin "1") (pinfunction "1_1") (pintype "passive"))
    )
    (net (code "52") (name "Net-(D232-A)") (class "Default")
      (node (ref "D232") (pin "1") (pinfunction "A_1") (pintype "passive"))
      (node (ref "S232") (pin "1") (pinfunction "1_1") (pintype "passive"))
    )
    (net (code "53") (name "Net-(D233-A)") (class "Default")
      (node (ref "D233") (pin "1") (pinfunction "A_1") (pintype "passive"))
      (node (ref "S233") (pin "1") (pinfunction "1_1") (pintype "passive"))
    )
    (net (code "54") (name "Net-(D234-A)") (class "Default")
      (node (ref "D234") (pin "1") (pinfunction "A_1") (pintype "passive"))
      (node (ref "S234") (pin "1") (pinfunction "1_1") (pintype "passive"))
    )
    (net (code "55") (name "Net-(D235-A)") (class "Default")
      (node (ref "D235") (pin "1") (pinfunction "A_1") (pintype "passive"))
      (node (ref "S235") (pin "1") (pinfunction "1_1") (pintype "passive"))
    )
    (net (code "56") (name "Net-(D236-A)") (class "Default")
      (node (ref "D236") (pin "1") (pinfunction "A_1") (pintype "passive"))
      (node (ref "S236") (pin "1") (pinfunction "1_1") (pintype "passive"))
    )
    (net (code "57") (name "Net-(D237-A)") (class "Default")
      (node (ref "D237") (pin "1") (pinfunction "A_1") (pintype "passive"))
      (node (ref "S237") (pin "1") (pinfunction "1_1") (pintype "passive"))
    )
    (net (code "58") (name "Net-(D238-A)") (class "Default")
      (node (ref "D238") (pin "1") (pinfunction "A_1") (pintype "passive"))
      (node (ref "S238") (pin "1") (pinfunction "1_1") (pintype "passive"))
    )
    (net (code "59") (name "Net-(D239-A)") (class "Default")
      (node (ref "D239") (pin "1") (pinfunction "A_1") (pintype "passive"))
      (node (ref "S239") (pin "1") (pinfunction "1_1") (pintype "passive"))
    )
    (net (code "60") (name "Net-(D240-A)") (class "Default")
      (node (ref "D240") (pin "1") (pinfunction "A_1") (pintype "passive"))
      (node (ref "S240") (pin "1") (pinfunction "1_1") (pintype "passive"))
    )
    (net (code "61") (name "Net-(D242-A)") (class "Default")
      (node (ref "D242") (pin "1") (pinfunction "A_1") (pintype "passive"))
      (node (ref "S242") (pin "2") (pinfunction "2_2") (pintype "passive"))
    )
    (net (code "62") (name "Net-(D243-A)") (class "Default")
      (node (ref "D243") (pin "1") (pinfunction "A_1") (pintype "passive"))
      (node (ref "S243") (pin "2") (pinfunction "2_2") (pintype "passive"))
    )
    (net (code "63") (name "Net-(D245-A)") (class "Default")
      (node (ref "D245") (pin "1") (pinfunction "A_1") (pintype "passive"))
      (node (ref "S245") (pin "1") (pinfunction "1_1") (pintype "passive"))
    )
    (net (code "64") (name "Net-(D246-A)") (class "Default")
      (node (ref "D246") (pin "1") (pinfunction "A_1") (pintype "passive"))
      (node (ref "S246") (pin "1") (pinfunction "1_1") (pintype "passive"))
    )
    (net (code "65") (name "Net-(D247-A)") (class "Default")
      (node (ref "D247") (pin "1") (pinfunction "A_1") (pintype "passive"))
      (node (ref "S247") (pin "1") (pinfunction "1_1") (pintype "passive"))
    )
    (net (code "66") (name "Net-(D248-A)") (class "Default")
      (node (ref "D248") (pin "1") (pinfunction "A_1") (pintype "passive"))
      (node (ref "S248") (pin "1") (pinfunction "1_1") (pintype "passive"))
    )
    (net (code "67") (name "Net-(D249-A)") (class "Default")
      (node (ref "D249") (pin "1") (pinfunction "A_1") (pintype "passive"))
      (node (ref "S249") (pin "1") (pinfunction "1_1") (pintype "passive"))
    )
    (net (code "68") (name "Net-(D250-A)") (class "Default")
      (node (ref "D250") (pin "1") (pinfunction "A_1") (pintype "passive"))
      (node (ref "S250") (pin "1") (pinfunction "1_1") (pintype "passive"))
    )
    (net (code "69") (name "Net-(D251-A)") (class "Default")
      (node (ref "D251") (pin "1") (pinfunction "A_1") (pintype "passive"))
      (node (ref "S251") (pin "1") (pinfunction "1_1") (pintype "passive"))
    )
    (net (code "70") (name "Net-(D252-A)") (class "Default")
      (node (ref "D252") (pin "1") (pinfunction "A_1") (pintype "passive"))
      (node (ref "S252") (pin "1") (pinfunction "1_1") (pintype "passive"))
    )
    (net (code "71") (name "Net-(D253-A)") (class "Default")
      (node (ref "D253") (pin "1") (pinfunction "A_1") (pintype "passive"))
      (node (ref "S253") (pin "1") (pinfunction "1_1") (pintype "passive"))
    )
    (net (code "72") (name "Net-(D254-A)") (class "Default")
      (node (ref "D254") (pin "1") (pinfunction "A_1") (pintype "passive"))
      (node (ref "S254") (pin "1") (pinfunction "1_1") (pintype "passive"))
    )
    (net (code "73") (name "Net-(D256-A)") (class "Default")
      (node (ref "D256") (pin "1") (pinfunction "A_1") (pintype "passive"))
      (node (ref "S256") (pin "1") (pinfunction "1_1") (pintype "passive"))
    )
    (net (code "74") (name "Net-(D257-A)") (class "Default")
      (node (ref "D257") (pin "1") (pinfunction "A_1") (pintype "passive"))
      (node (ref "S257") (pin "1") (pinfunction "1_1") (pintype "passive"))
    )
    (net (code "75") (name "Net-(D258-A)") (class "Default")
      (node (ref "D258") (pin "1") (pinfunction "A_1") (pintype "passive"))
      (node (ref "S258") (pin "1") (pinfunction "1_1") (pintype "passive"))
    )
    (net (code "76") (name "Net-(D259-A)") (class "Default")
      (node (ref "D259") (pin "1") (pinfunction "A_1") (pintype "passive"))
      (node (ref "S259") (pin "1") (pinfunction "1_1") (pintype "passive"))
    )
    (net (code "77") (name "Net-(D260-A)") (class "Default")
      (node (ref "D260") (pin "1") (pinfunction "A_1") (pintype "passive"))
      (node (ref "S260") (pin "1") (pinfunction "1_1") (pintype "passive"))
    )
    (net (code "78") (name "Net-(D262-A)") (class "Default")
      (node (ref "D262") (pin "1") (pinfunction "A_1") (pintype "passive"))
      (node (ref "S262") (pin "1") (pinfunction "1_1") (pintype "passive"))
    )
    (net (code "79") (name "Net-(D264-A)") (class "Default")
      (node (ref "D264") (pin "1") (pinfunction "A_1") (pintype "passive"))
      (node (ref "S264") (pin "1") (pinfunction "1_1") (pintype "passive"))
    )
    (net (code "80") (name "Net-(D265-A)") (class "Default")
      (node (ref "D265") (pin "1") (pinfunction "A_1") (pintype "passive"))
      (node (ref "S265") (pin "1") (pinfunction "1_1") (pintype "passive"))
    )
    (net (code "81") (name "Net-(D266-A)") (class "Default")
      (node (ref "D266") (pin "1") (pinfunction "A_1") (pintype "passive"))
      (node (ref "S266") (pin "1") (pinfunction "1_1") (pintype "passive"))
    )
    (net (code "82") (name "Net-(D269-A)") (class "Default")
      (node (ref "D269") (pin "1") (pinfunction "A_1") (pintype "passive"))
      (node (ref "S269") (pin "1") (pinfunction "1_1") (pintype "passive"))
    )
  )
)
